# E-Wuerfel.net
KiCad netlist of a schematic drawn in EAGLE
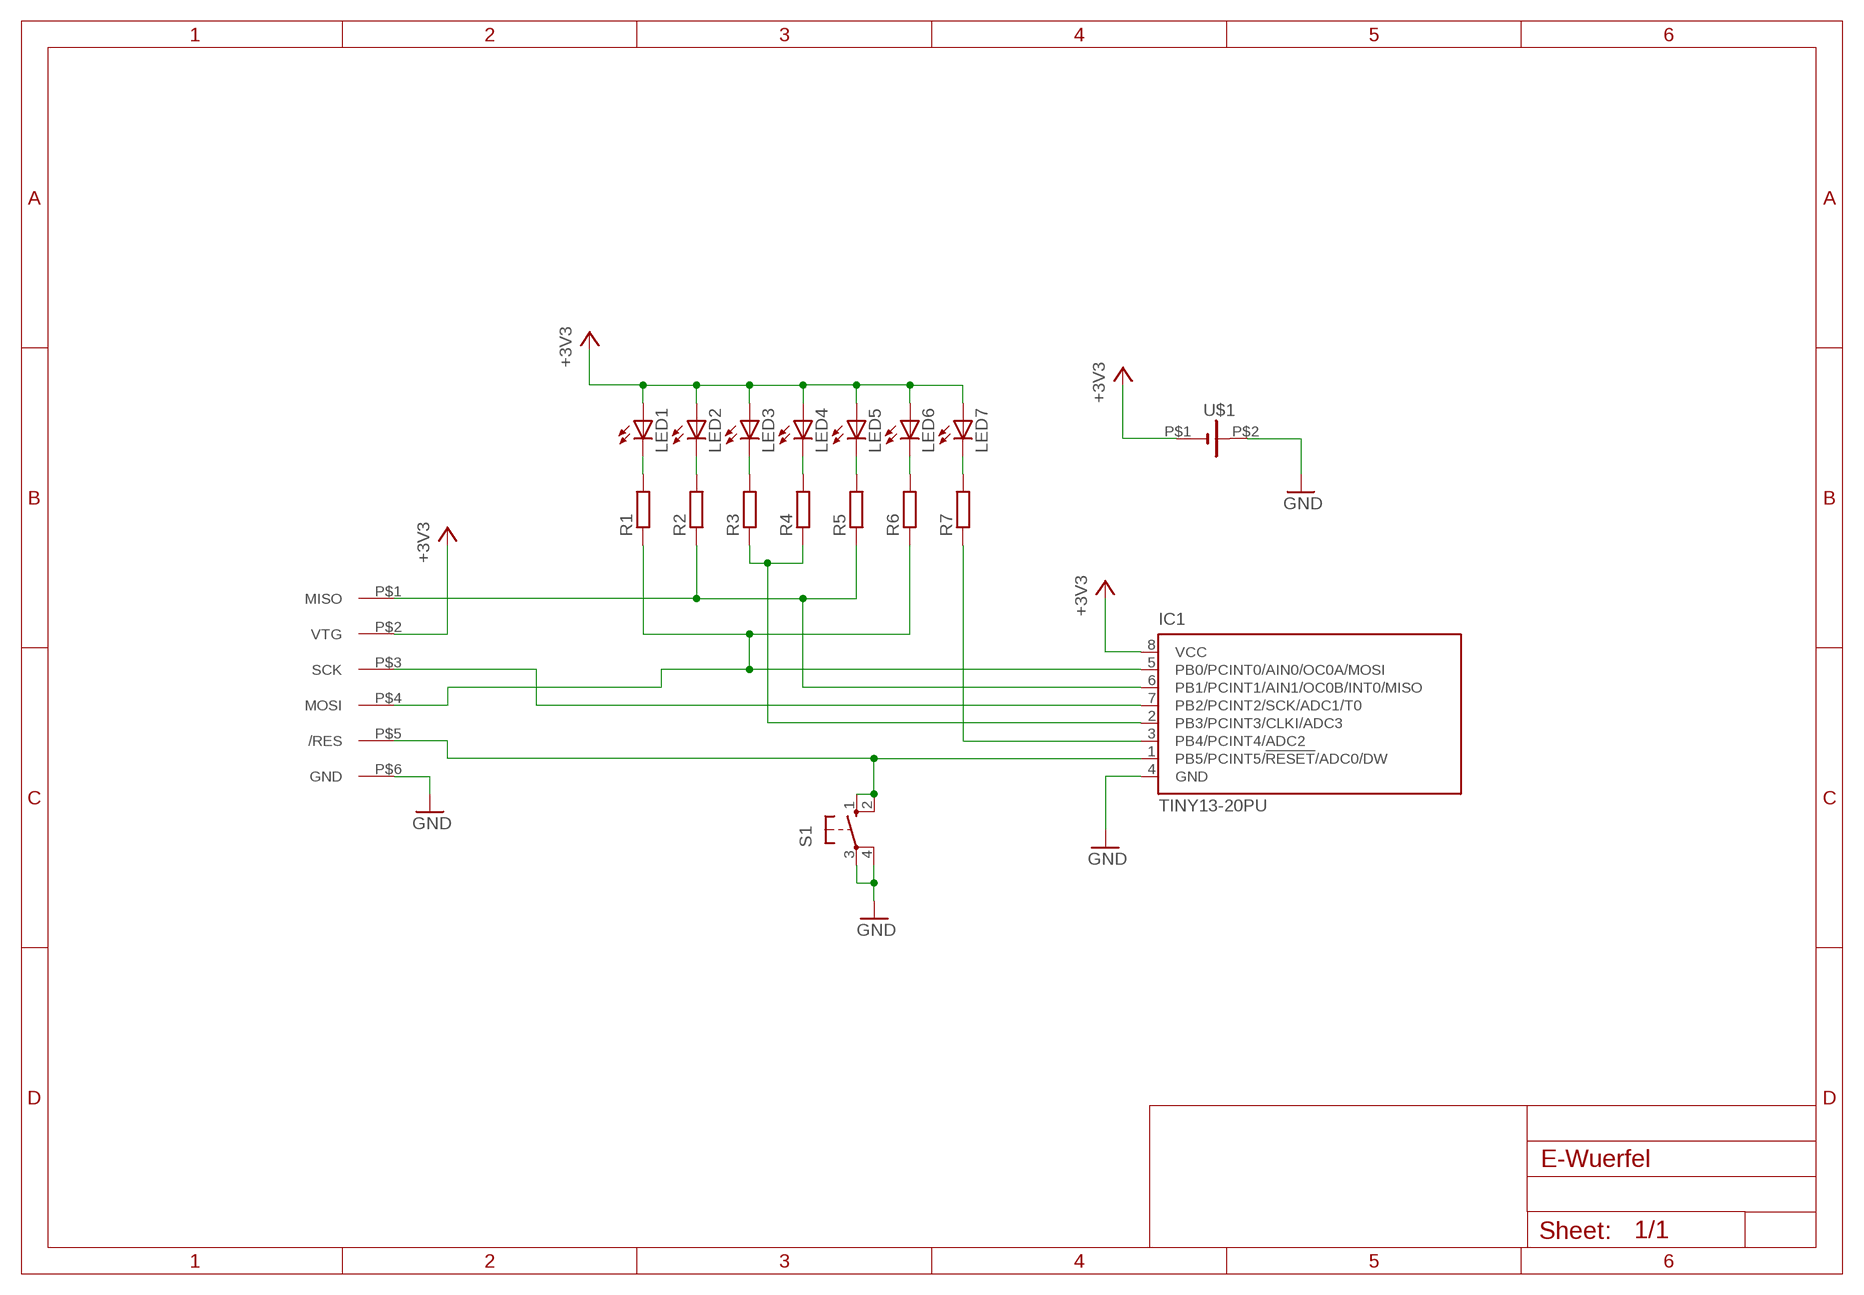
[diagram p0: schematic, sheet 1]

(export (version "E")
  (design (tool "Eeschema 10.0.6"))
  (components
    (comp (ref "IC1")
      (value "TINY13-20PU")
      (footprint "eagle-import:DIL08")
      (fields (field (name "MPN") "ATTINY13-20PU"))
      (libsource (lib "eagle-import") (part "TINY13PU-20"))
    )
    (comp (ref "LED1")
      (value "LED5MM")
      (footprint "eagle-import:LED5MM")
      (libsource (lib "eagle-import") (part "LED5MM"))
    )
    (comp (ref "LED2")
      (value "LED5MM")
      (footprint "eagle-import:LED5MM")
      (libsource (lib "eagle-import") (part "LED5MM"))
    )
    (comp (ref "LED3")
      (value "LED5MM")
      (footprint "eagle-import:LED5MM")
      (libsource (lib "eagle-import") (part "LED5MM"))
    )
    (comp (ref "LED4")
      (value "LED5MM")
      (footprint "eagle-import:LED5MM")
      (libsource (lib "eagle-import") (part "LED5MM"))
    )
    (comp (ref "LED5")
      (value "LED5MM")
      (footprint "eagle-import:LED5MM")
      (libsource (lib "eagle-import") (part "LED5MM"))
    )
    (comp (ref "LED6")
      (value "LED5MM")
      (footprint "eagle-import:LED5MM")
      (libsource (lib "eagle-import") (part "LED5MM"))
    )
    (comp (ref "LED7")
      (value "LED5MM")
      (footprint "eagle-import:LED5MM")
      (libsource (lib "eagle-import") (part "LED5MM"))
    )
    (comp (ref "R1")
      (value "R-EU_0207/7")
      (footprint "eagle-import:0207_7")
      (libsource (lib "eagle-import") (part "R-EU_0207/7"))
    )
    (comp (ref "R2")
      (value "R-EU_0207/7")
      (footprint "eagle-import:0207_7")
      (libsource (lib "eagle-import") (part "R-EU_0207/7"))
    )
    (comp (ref "R3")
      (value "R-EU_0207/7")
      (footprint "eagle-import:0207_7")
      (libsource (lib "eagle-import") (part "R-EU_0207/7"))
    )
    (comp (ref "R4")
      (value "R-EU_0207/7")
      (footprint "eagle-import:0207_7")
      (libsource (lib "eagle-import") (part "R-EU_0207/7"))
    )
    (comp (ref "R5")
      (value "R-EU_0207/7")
      (footprint "eagle-import:0207_7")
      (libsource (lib "eagle-import") (part "R-EU_0207/7"))
    )
    (comp (ref "R6")
      (value "R-EU_0207/7")
      (footprint "eagle-import:0207_7")
      (libsource (lib "eagle-import") (part "R-EU_0207/7"))
    )
    (comp (ref "R7")
      (value "R-EU_0207/7")
      (footprint "eagle-import:0207_7")
      (libsource (lib "eagle-import") (part "R-EU_0207/7"))
    )
    (comp (ref "S1")
      (value "10-XX")
      (footprint "eagle-import:B3F-10XX")
      (fields (field (name "MPN") "B3F-1000"))
      (libsource (lib "eagle-import") (part "10-XX"))
    )
    (comp (ref "U$1")
      (value "2XAA")
      (footprint "eagle-import:2AAMOUNT")
      (libsource (lib "eagle-import") (part "2XAA"))
    )
    (comp (ref "U$2")
      (value "AVRISP1.27")
      (footprint "eagle-import:2X6-127")
      (libsource (lib "eagle-import") (part "AVRISP1.27"))
    )
  )
  (nets
    (net (code "1") (name "+3V3") (class "Default")
      (node (ref "IC1") (pin "8") (pinfunction "VCC_8") (pintype "power_in"))
      (node (ref "LED1") (pin "A") (pinfunction "A_A") (pintype "passive"))
      (node (ref "LED2") (pin "A") (pinfunction "A_A") (pintype "passive"))
      (node (ref "LED3") (pin "A") (pinfunction "A_A") (pintype "passive"))
      (node (ref "LED4") (pin "A") (pinfunction "A_A") (pintype "passive"))
      (node (ref "LED5") (pin "A") (pinfunction "A_A") (pintype "passive"))
      (node (ref "LED6") (pin "A") (pinfunction "A_A") (pintype "passive"))
      (node (ref "LED7") (pin "A") (pinfunction "A_A") (pintype "passive"))
      (node (ref "U$1") (pin "P$1") (pinfunction "-_P$1") (pintype "passive"))
      (node (ref "U$2") (pin "P$2") (pinfunction "VTG_P$2") (pintype "bidirectional"))
    )
    (net (code "2") (name "GND") (class "Default")
      (node (ref "IC1") (pin "4") (pinfunction "GND_4") (pintype "power_in"))
      (node (ref "S1") (pin "3") (pinfunction "P_3") (pintype "passive"))
      (node (ref "S1") (pin "4") (pinfunction "P1_4") (pintype "passive"))
      (node (ref "U$1") (pin "P$2") (pinfunction "+_P$2") (pintype "passive"))
      (node (ref "U$2") (pin "P$6") (pinfunction "GND_P$6") (pintype "bidirectional"))
    )
    (net (code "3") (name "Net-(IC1-PB0{slash}PCINT0{slash}AIN0{slash}OC0A{slash}MOSI)") (class "Default")
      (node (ref "IC1") (pin "5") (pinfunction "PB0/PCINT0/AIN0/OC0A/MOSI_5") (pintype "bidirectional"))
      (node (ref "R1") (pin "1") (pinfunction "1_1") (pintype "passive"))
      (node (ref "R6") (pin "1") (pinfunction "1_1") (pintype "passive"))
      (node (ref "U$2") (pin "P$4") (pinfunction "MOSI_P$4") (pintype "bidirectional"))
    )
    (net (code "4") (name "Net-(IC1-PB1{slash}PCINT1{slash}AIN1{slash}OC0B{slash}INT0{slash}MISO)") (class "Default")
      (node (ref "IC1") (pin "6") (pinfunction "PB1/PCINT1/AIN1/OC0B/INT0/MISO_6") (pintype "bidirectional"))
      (node (ref "R2") (pin "1") (pinfunction "1_1") (pintype "passive"))
      (node (ref "R5") (pin "1") (pinfunction "1_1") (pintype "passive"))
      (node (ref "U$2") (pin "P$1") (pinfunction "MISO_P$1") (pintype "bidirectional"))
    )
    (net (code "5") (name "Net-(IC1-PB2{slash}PCINT2{slash}SCK{slash}ADC1{slash}T0)") (class "Default")
      (node (ref "IC1") (pin "7") (pinfunction "PB2/PCINT2/SCK/ADC1/T0_7") (pintype "bidirectional"))
      (node (ref "U$2") (pin "P$3") (pinfunction "SCK_P$3") (pintype "bidirectional"))
    )
    (net (code "6") (name "Net-(IC1-PB3{slash}PCINT3{slash}CLKI{slash}ADC3)") (class "Default")
      (node (ref "IC1") (pin "2") (pinfunction "PB3/PCINT3/CLKI/ADC3_2") (pintype "bidirectional"))
      (node (ref "R3") (pin "1") (pinfunction "1_1") (pintype "passive"))
      (node (ref "R4") (pin "1") (pinfunction "1_1") (pintype "passive"))
    )
    (net (code "7") (name "Net-(IC1-PB4{slash}PCINT4{slash}ADC2)") (class "Default")
      (node (ref "IC1") (pin "3") (pinfunction "PB4/PCINT4/ADC2_3") (pintype "bidirectional"))
      (node (ref "R7") (pin "1") (pinfunction "1_1") (pintype "passive"))
    )
    (net (code "8") (name "Net-(IC1-PB5{slash}PCINT5{slash}~{RESET}{slash}ADC0{slash}DW)") (class "Default")
      (node (ref "IC1") (pin "1") (pinfunction "PB5/PCINT5/~{RESET}/ADC0/DW_1") (pintype "bidirectional"))
      (node (ref "S1") (pin "1") (pinfunction "S_1") (pintype "passive"))
      (node (ref "S1") (pin "2") (pinfunction "S1_2") (pintype "passive"))
      (node (ref "U$2") (pin "P$5") (pinfunction "/RES_P$5") (pintype "bidirectional"))
    )
    (net (code "9") (name "Net-(LED1-C)") (class "Default")
      (node (ref "LED1") (pin "K") (pinfunction "C_K") (pintype "passive"))
      (node (ref "R1") (pin "2") (pinfunction "2_2") (pintype "passive"))
    )
    (net (code "10") (name "Net-(LED2-C)") (class "Default")
      (node (ref "LED2") (pin "K") (pinfunction "C_K") (pintype "passive"))
      (node (ref "R2") (pin "2") (pinfunction "2_2") (pintype "passive"))
    )
    (net (code "11") (name "Net-(LED3-C)") (class "Default")
      (node (ref "LED3") (pin "K") (pinfunction "C_K") (pintype "passive"))
      (node (ref "R3") (pin "2") (pinfunction "2_2") (pintype "passive"))
    )
    (net (code "12") (name "Net-(LED4-C)") (class "Default")
      (node (ref "LED4") (pin "K") (pinfunction "C_K") (pintype "passive"))
      (node (ref "R4") (pin "2") (pinfunction "2_2") (pintype "passive"))
    )
    (net (code "13") (name "Net-(LED5-C)") (class "Default")
      (node (ref "LED5") (pin "K") (pinfunction "C_K") (pintype "passive"))
      (node (ref "R5") (pin "2") (pinfunction "2_2") (pintype "passive"))
    )
    (net (code "14") (name "Net-(LED6-C)") (class "Default")
      (node (ref "LED6") (pin "K") (pinfunction "C_K") (pintype "passive"))
      (node (ref "R6") (pin "2") (pinfunction "2_2") (pintype "passive"))
    )
    (net (code "15") (name "Net-(LED7-C)") (class "Default")
      (node (ref "LED7") (pin "K") (pinfunction "C_K") (pintype "passive"))
      (node (ref "R7") (pin "2") (pinfunction "2_2") (pintype "passive"))
    )
  )
)
